# SCH-10-Power_Connectors.net
KiCad netlist of a schematic drawn in Altium Designer
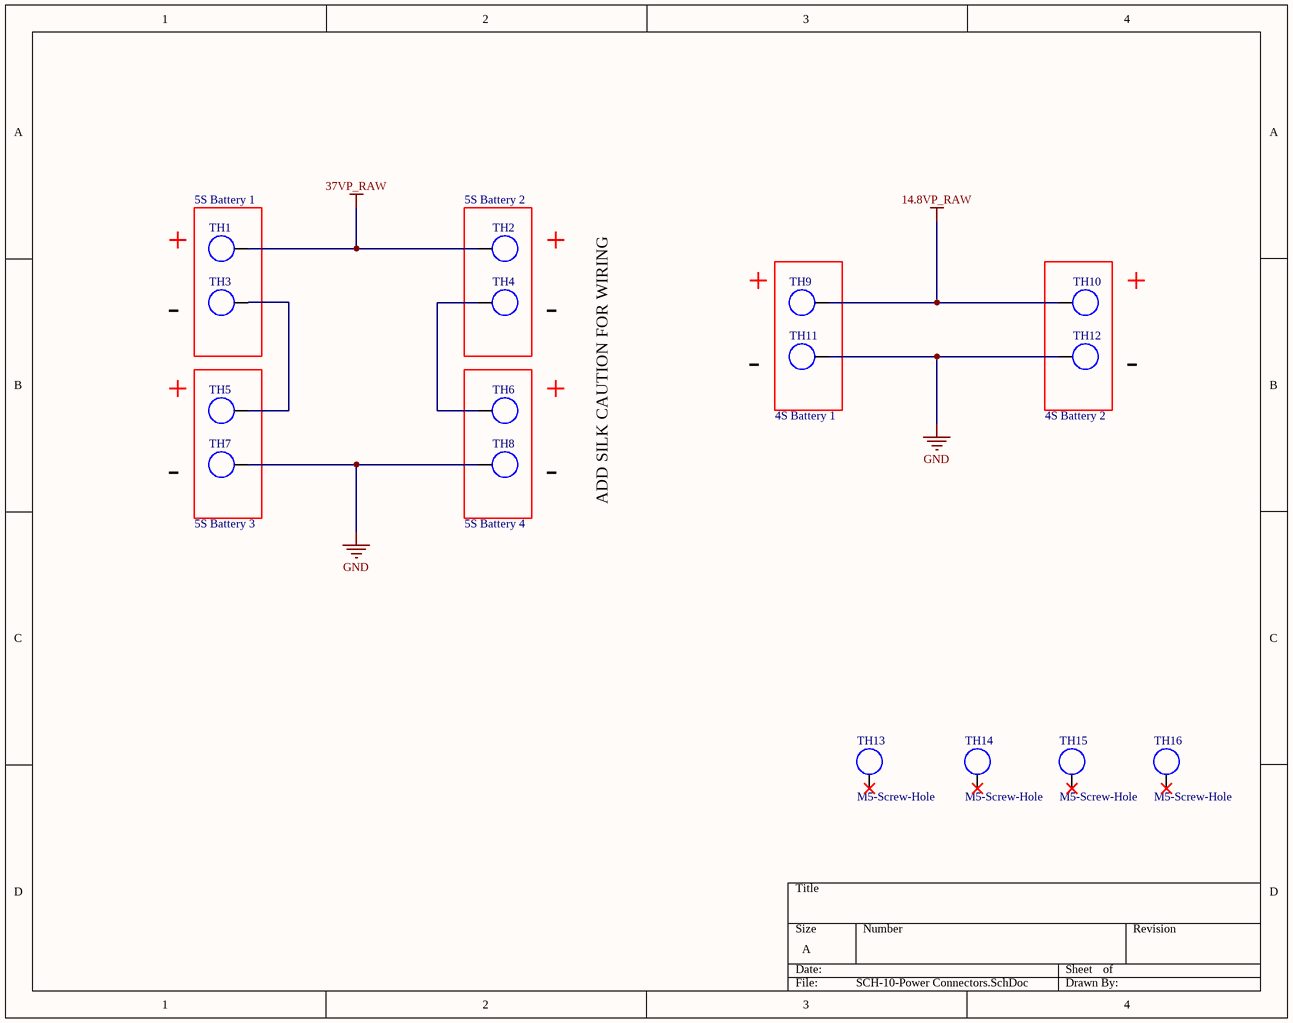
[diagram p0: SCH-10-Power Connectors.SchDoc]

(export (version "E")
  (design (tool "Eeschema 10.0.6"))
  (components
    (comp (ref "TH1")
      (value "12AWG_TH")
      (footprint "12AWG_Wire_TH")
      (libsource (lib "RSX_Mechanicals") (part "12AWG_TH"))
    )
    (comp (ref "TH2")
      (value "12AWG_TH")
      (footprint "12AWG_Wire_TH")
      (libsource (lib "RSX_Mechanicals") (part "12AWG_TH"))
    )
    (comp (ref "TH3")
      (value "12AWG_TH")
      (footprint "12AWG_Wire_TH")
      (libsource (lib "RSX_Mechanicals") (part "12AWG_TH"))
    )
    (comp (ref "TH4")
      (value "12AWG_TH")
      (footprint "12AWG_Wire_TH")
      (libsource (lib "RSX_Mechanicals") (part "12AWG_TH"))
    )
    (comp (ref "TH5")
      (value "12AWG_TH")
      (footprint "12AWG_Wire_TH")
      (libsource (lib "RSX_Mechanicals") (part "12AWG_TH"))
    )
    (comp (ref "TH6")
      (value "12AWG_TH")
      (footprint "12AWG_Wire_TH")
      (libsource (lib "RSX_Mechanicals") (part "12AWG_TH"))
    )
    (comp (ref "TH7")
      (value "12AWG_TH")
      (footprint "12AWG_Wire_TH")
      (libsource (lib "RSX_Mechanicals") (part "12AWG_TH"))
    )
    (comp (ref "TH8")
      (value "12AWG_TH")
      (footprint "12AWG_Wire_TH")
      (libsource (lib "RSX_Mechanicals") (part "12AWG_TH"))
    )
    (comp (ref "TH9")
      (value "10AWG_TH")
      (footprint "10AWG_Wire_TH")
      (libsource (lib "RSX_Mechanicals") (part "10AWG_TH"))
    )
    (comp (ref "TH10")
      (value "10AWG_TH")
      (footprint "10AWG_Wire_TH")
      (libsource (lib "RSX_Mechanicals") (part "10AWG_TH"))
    )
    (comp (ref "TH11")
      (value "10AWG_TH")
      (footprint "10AWG_Wire_TH")
      (libsource (lib "RSX_Mechanicals") (part "10AWG_TH"))
    )
    (comp (ref "TH12")
      (value "10AWG_TH")
      (footprint "10AWG_Wire_TH")
      (libsource (lib "RSX_Mechanicals") (part "10AWG_TH"))
    )
    (comp (ref "TH13")
      (value "M5-Screw-Hole")
      (footprint "M5_Screw_Hole")
      (libsource (lib "RSX_Mechanicals") (part "M5-Screw-Hole"))
    )
    (comp (ref "TH14")
      (value "M5-Screw-Hole")
      (footprint "M5_Screw_Hole")
      (libsource (lib "RSX_Mechanicals") (part "M5-Screw-Hole"))
    )
    (comp (ref "TH15")
      (value "M5-Screw-Hole")
      (footprint "M5_Screw_Hole")
      (libsource (lib "RSX_Mechanicals") (part "M5-Screw-Hole"))
    )
    (comp (ref "TH16")
      (value "M5-Screw-Hole")
      (footprint "M5_Screw_Hole")
      (libsource (lib "RSX_Mechanicals") (part "M5-Screw-Hole"))
    )
  )
  (nets
    (net (code "1") (name "14.8VP_RAW") (class "Default")
      (node (ref "TH10") (pin "1") (pinfunction "1_1") (pintype "passive"))
      (node (ref "TH9") (pin "1") (pinfunction "1_1") (pintype "passive"))
    )
    (net (code "2") (name "37VP_RAW") (class "Default")
      (node (ref "TH1") (pin "1") (pinfunction "1_1") (pintype "passive"))
      (node (ref "TH2") (pin "1") (pinfunction "1_1") (pintype "passive"))
    )
    (net (code "3") (name "GND") (class "Default")
      (node (ref "TH11") (pin "1") (pinfunction "1_1") (pintype "passive"))
      (node (ref "TH12") (pin "1") (pinfunction "1_1") (pintype "passive"))
      (node (ref "TH7") (pin "1") (pinfunction "1_1") (pintype "passive"))
      (node (ref "TH8") (pin "1") (pinfunction "1_1") (pintype "passive"))
    )
    (net (code "4") (name "Net-(TH3-Pad1)") (class "Default")
      (node (ref "TH3") (pin "1") (pinfunction "1_1") (pintype "passive"))
      (node (ref "TH5") (pin "1") (pinfunction "1_1") (pintype "passive"))
    )
    (net (code "5") (name "Net-(TH4-Pad1)") (class "Default")
      (node (ref "TH4") (pin "1") (pinfunction "1_1") (pintype "passive"))
      (node (ref "TH6") (pin "1") (pinfunction "1_1") (pintype "passive"))
    )
    (net (code "6") (name "unconnected-(TH13-Pad1)") (class "Default")
      (node (ref "TH13") (pin "1") (pinfunction "1_1") (pintype "passive+no_connect"))
    )
    (net (code "7") (name "unconnected-(TH14-Pad1)") (class "Default")
      (node (ref "TH14") (pin "1") (pinfunction "1_1") (pintype "passive+no_connect"))
    )
    (net (code "8") (name "unconnected-(TH15-Pad1)") (class "Default")
      (node (ref "TH15") (pin "1") (pinfunction "1_1") (pintype "passive+no_connect"))
    )
    (net (code "9") (name "unconnected-(TH16-Pad1)") (class "Default")
      (node (ref "TH16") (pin "1") (pinfunction "1_1") (pintype "passive+no_connect"))
    )
  )
)
